# IoT_Greenhouse_V1_0_A_-_Pwr_Input.net
KiCad netlist of a schematic drawn in Altium Designer
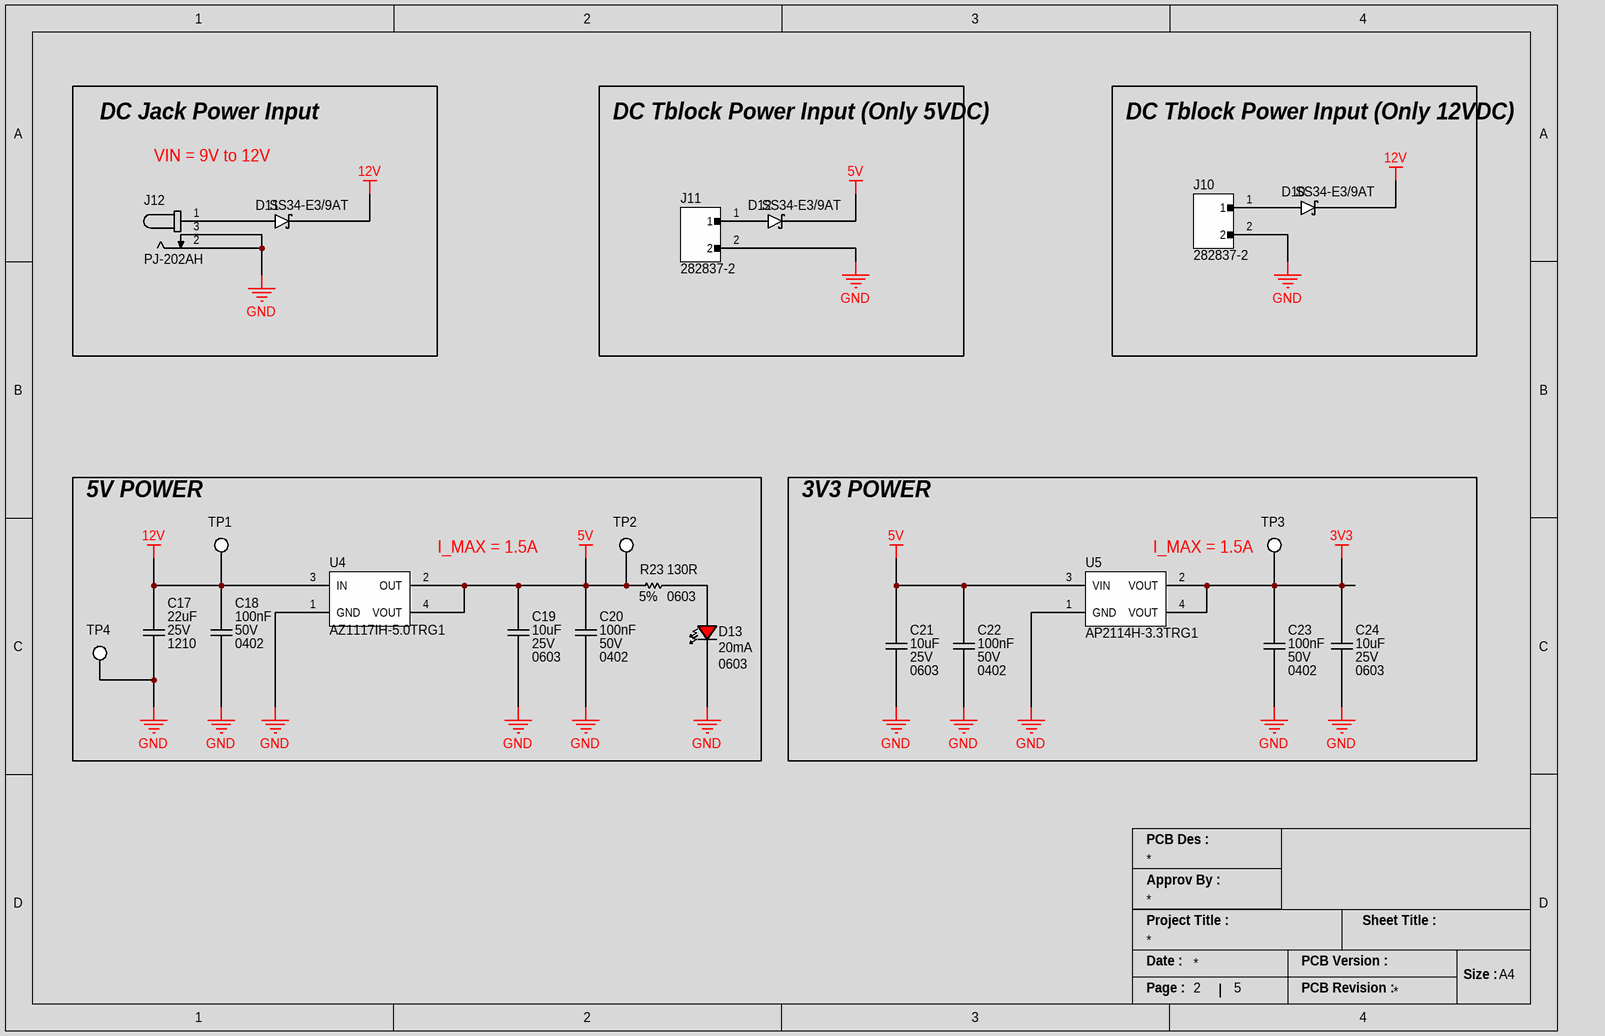
[diagram p0: IoT_Greenhouse V1.0 A - Pwr Input.SchDoc]

(export (version "E")
  (design (tool "Eeschema 10.0.6"))
  (components
    (comp (ref "C17")
      (value "GRM32ER71E226KE15L")
      (footprint "CAP_1210_CAPC3225X270N")
      (description "Multilayer Ceramic Capacitor, 22 uF, 25 V, ± 10%, X7R, 1210 [3225 Metric]")
      (fields
        (field (name "MANUFACTURER") "Murata")
        (field (name "TOLERANCE") "10%")
        (field (name "VOLTAGE RATING") "25V")
        (field (name "CAPACITANCE") "22uF")
        (field (name "CASE/PACKAGE") "1210")
      )
      (libsource (lib "Electronic Devices_LIB") (part "CAP_22UF_25V_X7R_1210"))
    )
    (comp (ref "C18")
      (value "GRM155R71H104KE14D")
      (footprint "CAP_0402_CAPC1005X05N")
      (description "Multilayer Ceramic Capacitor, 0.1 uF, 16 V, ± 10%, X7R, 0402 [1005 Metric]")
      (fields
        (field (name "MANUFACTURER") "Murata")
        (field (name "TOLERANCE") "10%")
        (field (name "VOLTAGE RATING") "50V")
        (field (name "CAPACITANCE") "100nF")
        (field (name "CASE/PACKAGE") "0402")
      )
      (libsource (lib "Electronic Devices_LIB") (part "CAP_100NF_50V_X7R_0402"))
    )
    (comp (ref "C19")
      (value "GRM188R61E106MA73D")
      (footprint "CAP_0603_CAPC1608X08N")
      (description "Multilayer Ceramic Capacitor, 10 uF, 25 V, ± 20%, X5R, 0603 [1608 Metric]")
      (fields
        (field (name "MANUFACTURER") "Murata")
        (field (name "TOLERANCE") "20%")
        (field (name "CASE/PACKAGE") "0603")
        (field (name "CAPACITANCE") "10uF")
        (field (name "VOLTAGE RATING") "25V")
      )
      (libsource (lib "Electronic Devices_LIB") (part "CAP_10UF_25V_X5R_0603"))
    )
    (comp (ref "C20")
      (value "GRM155R71H104KE14D")
      (footprint "CAP_0402_CAPC1005X05N")
      (description "Multilayer Ceramic Capacitor, 0.1 uF, 16 V, ± 10%, X7R, 0402 [1005 Metric]")
      (fields
        (field (name "MANUFACTURER") "Murata")
        (field (name "TOLERANCE") "10%")
        (field (name "VOLTAGE RATING") "50V")
        (field (name "CAPACITANCE") "100nF")
        (field (name "CASE/PACKAGE") "0402")
      )
      (libsource (lib "Electronic Devices_LIB") (part "CAP_100NF_50V_X7R_0402"))
    )
    (comp (ref "C21")
      (value "GRM188R61E106MA73D")
      (footprint "CAP_0603_CAPC1608X08N")
      (description "Multilayer Ceramic Capacitor, 10 uF, 25 V, ± 20%, X5R, 0603 [1608 Metric]")
      (fields
        (field (name "MANUFACTURER") "Murata")
        (field (name "TOLERANCE") "20%")
        (field (name "CASE/PACKAGE") "0603")
        (field (name "CAPACITANCE") "10uF")
        (field (name "VOLTAGE RATING") "25V")
      )
      (libsource (lib "Electronic Devices_LIB") (part "CAP_10UF_25V_X5R_0603"))
    )
    (comp (ref "C22")
      (value "GRM155R71H104KE14D")
      (footprint "CAP_0402_CAPC1005X05N")
      (description "Multilayer Ceramic Capacitor, 0.1 uF, 16 V, ± 10%, X7R, 0402 [1005 Metric]")
      (fields
        (field (name "MANUFACTURER") "Murata")
        (field (name "TOLERANCE") "10%")
        (field (name "VOLTAGE RATING") "50V")
        (field (name "CAPACITANCE") "100nF")
        (field (name "CASE/PACKAGE") "0402")
      )
      (libsource (lib "Electronic Devices_LIB") (part "CAP_100NF_50V_X7R_0402"))
    )
    (comp (ref "C23")
      (value "GRM155R71H104KE14D")
      (footprint "CAP_0402_CAPC1005X05N")
      (description "Multilayer Ceramic Capacitor, 0.1 uF, 16 V, ± 10%, X7R, 0402 [1005 Metric]")
      (fields
        (field (name "MANUFACTURER") "Murata")
        (field (name "TOLERANCE") "10%")
        (field (name "VOLTAGE RATING") "50V")
        (field (name "CAPACITANCE") "100nF")
        (field (name "CASE/PACKAGE") "0402")
      )
      (libsource (lib "Electronic Devices_LIB") (part "CAP_100NF_50V_X7R_0402"))
    )
    (comp (ref "C24")
      (value "GRM188R61E106MA73D")
      (footprint "CAP_0603_CAPC1608X08N")
      (description "Multilayer Ceramic Capacitor, 10 uF, 25 V, ± 20%, X5R, 0603 [1608 Metric]")
      (fields
        (field (name "MANUFACTURER") "Murata")
        (field (name "TOLERANCE") "20%")
        (field (name "CASE/PACKAGE") "0603")
        (field (name "CAPACITANCE") "10uF")
        (field (name "VOLTAGE RATING") "25V")
      )
      (libsource (lib "Electronic Devices_LIB") (part "CAP_10UF_25V_X5R_0603"))
    )
    (comp (ref "D10")
      (value "SS34-E3/9AT")
      (footprint "DIO_Vishay_SMC_MFG")
      (description "Rectifier Diode, schottky, 40V V(Rrm), do-214Ab / Smc")
      (fields (field (name "MANUFACTURER") "Vishay Semiconductors"))
      (libsource (lib "Electronic Devices_LIB") (part "DIO_SCTKY_40V_3A"))
    )
    (comp (ref "D11")
      (value "SS34-E3/9AT")
      (footprint "DIO_Vishay_SMC_MFG")
      (description "Rectifier Diode, schottky, 40V V(Rrm), do-214Ab / Smc")
      (fields (field (name "MANUFACTURER") "Vishay Semiconductors"))
      (libsource (lib "Electronic Devices_LIB") (part "DIO_SCTKY_40V_3A"))
    )
    (comp (ref "D12")
      (value "SS34-E3/9AT")
      (footprint "DIO_Vishay_SMC_MFG")
      (description "Rectifier Diode, schottky, 40V V(Rrm), do-214Ab / Smc")
      (fields (field (name "MANUFACTURER") "Vishay Semiconductors"))
      (libsource (lib "Electronic Devices_LIB") (part "DIO_SCTKY_40V_3A"))
    )
    (comp (ref "D13")
      (value "LTST-C190KRKT")
      (footprint "LED_0603-RED-0.75mm")
      (description "LED,  LTST-C190KRKT")
      (fields
        (field (name "MANUFACTURER") "Vishay Lite-On")
        (field (name "TEST CURRENT") "20mA")
        (field (name "CASE/PACKAGE") "0603")
      )
      (libsource (lib "Electronic Devices_LIB") (part "LED_DIO_RED_20mA_0603"))
    )
    (comp (ref "J10")
      (value "282837-2")
      (footprint "CONN_TBLOCK_2P_{backslash}2828372")
      (description "Connector, Terminal Block; Wire Receptacle; 2 Pos.; 16-30 AWG; 0.2 in. CL; Side;")
      (fields (field (name "MANUFACTURER") "TE Connectivity") (field (name "VOLTAGE") "300V"))
      (libsource (lib "Electronic Devices_LIB") (part "CONN_TBLOCK_2P_5.08mm_282837-2"))
    )
    (comp (ref "J11")
      (value "282837-2")
      (footprint "CONN_TBLOCK_2P_{backslash}2828372")
      (description "Connector, Terminal Block; Wire Receptacle; 2 Pos.; 16-30 AWG; 0.2 in. CL; Side;")
      (fields (field (name "MANUFACTURER") "TE Connectivity") (field (name "VOLTAGE") "300V"))
      (libsource (lib "Electronic Devices_LIB") (part "CONN_TBLOCK_2P_5.08mm_282837-2"))
    )
    (comp (ref "J12")
      (value "PJ-202AH")
      (footprint "CONN_CUI_PJ-202AH")
      (description "2.0 x 6.5 mm, 5.0 A, Horizontal, Through Hole, Kinked Pins, Dc Power Jack Connector")
      (fields (field (name "MANUFACTURER") "CUI Devices"))
      (libsource (lib "Electronic Devices_LIB") (part "CONN_DC_JACK_2X6.5mm_PJ-202AH"))
    )
    (comp (ref "R23")
      (value "RC0603JR-07130RL")
      (footprint "RES_0603_RESC1608X04N")
      (description "Res Thick Film 0603 130 Ohm 5% 1/10W ±100ppm/°C Molded SMD SMD Paper T/R")
      (fields
        (field (name "MANUFACTURER") "Yageo")
        (field (name "TOLERANCE") "5%")
        (field (name "RESISTENCE") "130R")
        (field (name "CASE/PACKCAGE") "0603")
      )
      (libsource (lib "Electronic Devices_LIB") (part "RES_130R_5%_100mW_0603"))
    )
    (comp (ref "TP1")
      (value "NO COMPONENT")
      (footprint "TP_PAD_1.6MM_SMD_ROUND")
      (description "Test Point, SMD pad, round, 1.5mm, 1.6mm, 3mm diameter")
      (libsource (lib "Electronic Devices_LIB") (part "TP_PAD_SMD_Round"))
    )
    (comp (ref "TP2")
      (value "NO COMPONENT")
      (footprint "TP_PAD_1.6MM_SMD_ROUND")
      (description "Test Point, SMD pad, round, 1.5mm, 1.6mm, 3mm diameter")
      (libsource (lib "Electronic Devices_LIB") (part "TP_PAD_SMD_Round"))
    )
    (comp (ref "TP3")
      (value "NO COMPONENT")
      (footprint "TP_PAD_1.6MM_SMD_ROUND")
      (description "Test Point, SMD pad, round, 1.5mm, 1.6mm, 3mm diameter")
      (libsource (lib "Electronic Devices_LIB") (part "TP_PAD_SMD_Round"))
    )
    (comp (ref "TP4")
      (value "NO COMPONENT")
      (footprint "TP_PAD_1.6MM_SMD_ROUND")
      (description "Test Point, SMD pad, round, 1.5mm, 1.6mm, 3mm diameter")
      (libsource (lib "Electronic Devices_LIB") (part "TP_PAD_SMD_Round"))
    )
    (comp (ref "U4")
      (value "AZ1117IH-5.0TRG1")
      (footprint "IC_REG_SOT230P700X180-4N")
      (description "LDO Regulator Pos 5V 1A 3-Pin SOT-223 T/R")
      (fields (field (name "MANUFACTURER") "Diodes"))
      (libsource (lib "Electronic Devices_LIB") (part "IC_REG_LDO_5V_1A_AZ1117IH-5.0TRG1"))
    )
    (comp (ref "U5")
      (value "AP2114H-3.3TRG1")
      (footprint "IC_REG_SOT230P700X180-4N")
      (description "IC REG LDO 3.3V 1A SOT223")
      (fields (field (name "MANUFACTURER") "Diodes"))
      (libsource (lib "Electronic Devices_LIB") (part "IC_REG_LDO_3.3V_1A_AP2114H-3.3TRG1"))
    )
  )
  (nets
    (net (code "1") (name "3V3") (class "Default")
      (node (ref "C23") (pin "2") (pinfunction "2_2") (pintype "passive"))
      (node (ref "C24") (pin "2") (pinfunction "2_2") (pintype "passive"))
      (node (ref "TP3") (pin "1") (pinfunction "1_1") (pintype "passive"))
      (node (ref "U5") (pin "2") (pinfunction "VOUT_2") (pintype "passive"))
      (node (ref "U5") (pin "4") (pinfunction "VOUT_4") (pintype "passive"))
    )
    (net (code "2") (name "5V") (class "Default")
      (node (ref "C19") (pin "2") (pinfunction "2_2") (pintype "passive"))
      (node (ref "C20") (pin "2") (pinfunction "2_2") (pintype "passive"))
      (node (ref "C21") (pin "2") (pinfunction "2_2") (pintype "passive"))
      (node (ref "C22") (pin "2") (pinfunction "2_2") (pintype "passive"))
      (node (ref "D12") (pin "1") (pinfunction "K_1") (pintype "passive"))
      (node (ref "R23") (pin "1") (pinfunction "1_1") (pintype "passive"))
      (node (ref "TP2") (pin "1") (pinfunction "1_1") (pintype "passive"))
      (node (ref "U4") (pin "2") (pinfunction "OUT_2") (pintype "passive"))
      (node (ref "U4") (pin "4") (pinfunction "VOUT_4") (pintype "passive"))
      (node (ref "U5") (pin "3") (pinfunction "VIN_3") (pintype "passive"))
    )
    (net (code "3") (name "12V") (class "Default")
      (node (ref "C17") (pin "2") (pinfunction "2_2") (pintype "passive"))
      (node (ref "C18") (pin "2") (pinfunction "2_2") (pintype "passive"))
      (node (ref "D10") (pin "1") (pinfunction "K_1") (pintype "passive"))
      (node (ref "D11") (pin "1") (pinfunction "K_1") (pintype "passive"))
      (node (ref "TP1") (pin "1") (pinfunction "1_1") (pintype "passive"))
      (node (ref "U4") (pin "3") (pinfunction "IN_3") (pintype "passive"))
    )
    (net (code "4") (name "GND") (class "Default")
      (node (ref "C17") (pin "1") (pinfunction "1_1") (pintype "passive"))
      (node (ref "C18") (pin "1") (pinfunction "1_1") (pintype "passive"))
      (node (ref "C19") (pin "1") (pinfunction "1_1") (pintype "passive"))
      (node (ref "C20") (pin "1") (pinfunction "1_1") (pintype "passive"))
      (node (ref "C21") (pin "1") (pinfunction "1_1") (pintype "passive"))
      (node (ref "C22") (pin "1") (pinfunction "1_1") (pintype "passive"))
      (node (ref "C23") (pin "1") (pinfunction "1_1") (pintype "passive"))
      (node (ref "C24") (pin "1") (pinfunction "1_1") (pintype "passive"))
      (node (ref "D13") (pin "1") (pinfunction "C_1") (pintype "passive"))
      (node (ref "J10") (pin "2") (pinfunction "2_2") (pintype "passive"))
      (node (ref "J11") (pin "2") (pinfunction "2_2") (pintype "passive"))
      (node (ref "J12") (pin "2") (pinfunction "2_2") (pintype "passive"))
      (node (ref "J12") (pin "3") (pinfunction "3_3") (pintype "passive"))
      (node (ref "TP4") (pin "1") (pinfunction "1_1") (pintype "passive"))
      (node (ref "U4") (pin "1") (pinfunction "GND_1") (pintype "passive"))
      (node (ref "U5") (pin "1") (pinfunction "GND_1") (pintype "passive"))
    )
    (net (code "5") (name "Net-(D10-A)") (class "Default")
      (node (ref "D10") (pin "2") (pinfunction "A_2") (pintype "passive"))
      (node (ref "J10") (pin "1") (pinfunction "1_1") (pintype "passive"))
    )
    (net (code "6") (name "Net-(D11-A)") (class "Default")
      (node (ref "D11") (pin "2") (pinfunction "A_2") (pintype "passive"))
      (node (ref "J12") (pin "1") (pinfunction "1_1") (pintype "passive"))
    )
    (net (code "7") (name "Net-(D12-A)") (class "Default")
      (node (ref "D12") (pin "2") (pinfunction "A_2") (pintype "passive"))
      (node (ref "J11") (pin "1") (pinfunction "1_1") (pintype "passive"))
    )
    (net (code "8") (name "Net-(D13-A)") (class "Default")
      (node (ref "D13") (pin "2") (pinfunction "A_2") (pintype "passive"))
      (node (ref "R23") (pin "2") (pinfunction "2_2") (pintype "passive"))
    )
  )
)
